# 16-TemHumdIr.net
KiCad netlist of a schematic drawn in Altium Designer
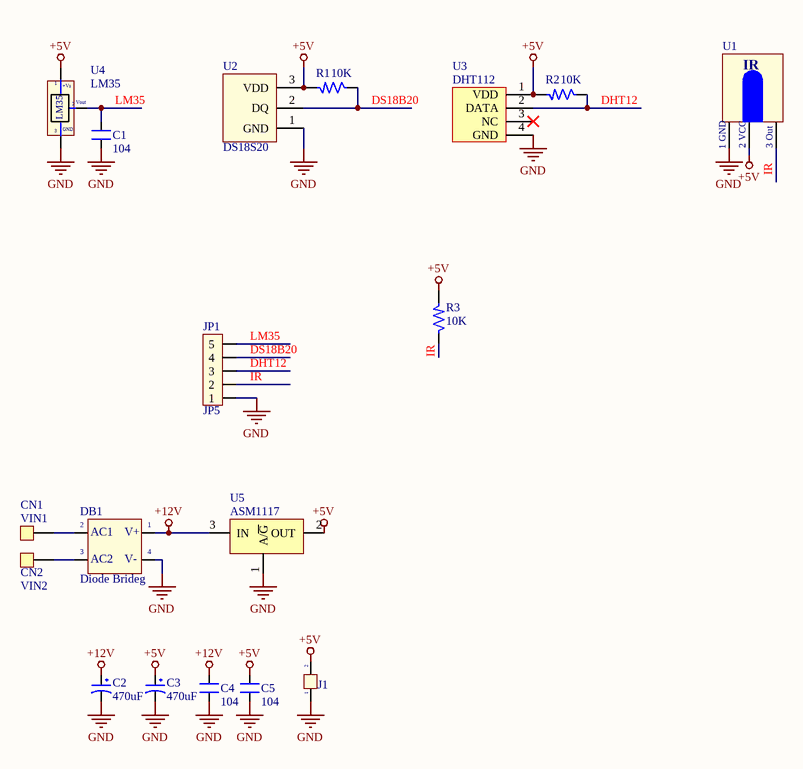
[diagram p0: 16-TemHumdIr.SchDoc]

(export (version "E")
  (design (tool "Eeschema 10.0.6"))
  (components
    (comp (ref "C1")
      (value "104")
      (footprint "C-0805")
      (fields (field (name "DESIGNED BY") "VanDungEvn"))
      (libsource (lib "syhaunguyen") (part "CN"))
    )
    (comp (ref "C2")
      (value "470uF")
      (footprint "C-ALU-D6.5")
      (description "Cap P  0,1uF < 22uF , 16 - 50V")
      (libsource (lib "PART") (part "CP1"))
    )
    (comp (ref "C3")
      (value "470uF")
      (footprint "C-ALU-D6.5")
      (description "Cap P  0,1uF < 22uF , 16 - 50V")
      (libsource (lib "PART") (part "CP1"))
    )
    (comp (ref "C4")
      (value "104")
      (footprint "C-0805")
      (fields (field (name "DESIGNED BY") "VanDungEvn"))
      (libsource (lib "syhaunguyen") (part "CN"))
    )
    (comp (ref "C5")
      (value "104")
      (footprint "C-0805")
      (fields (field (name "DESIGNED BY") "VanDungEvn"))
      (libsource (lib "syhaunguyen") (part "CN"))
    )
    (comp (ref "CN1")
      (value "VIN1")
      (footprint "M3")
      (libsource (lib "doAnTotNghiep2017Lib") (part "COCDONGM3"))
    )
    (comp (ref "CN2")
      (value "VIN2")
      (footprint "M3")
      (libsource (lib "doAnTotNghiep2017Lib") (part "COCDONGM3"))
    )
    (comp (ref "DB1")
      (value "Diode Brideg")
      (footprint "D-DB-1A-SMD")
      (description "Convert AC to DC voltage, 4 pin")
      (libsource (lib "PART") (part "DB"))
    )
    (comp (ref "J1") (value "Jumper 2") (footprint "JP2") (libsource (lib "syhaunguyen") (part "JP 2")))
    (comp (ref "JP1") (value "JP5") (footprint "JP5") (libsource (lib "syhaunguyen") (part "JP5")))
    (comp (ref "R1")
      (value "10K")
      (footprint "R-0805")
      (description "Resistor 1/4W")
      (libsource (lib "syhaunguyen") (part "R"))
    )
    (comp (ref "R2")
      (value "10K")
      (footprint "R-0805")
      (description "Resistor 1/4W")
      (libsource (lib "syhaunguyen") (part "R"))
    )
    (comp (ref "R3")
      (value "10K")
      (footprint "R-0805")
      (description "Resistor 1/4W")
      (libsource (lib "syhaunguyen") (part "R"))
    )
    (comp (ref "U1")
      (value "IR1")
      (footprint "IR-TSOP1133")
      (description "Receiver Infraed IC")
      (libsource (lib "PART") (part "IR1"))
    )
    (comp (ref "U2")
      (value "DS18S20")
      (footprint "TO-92AB")
      (description "High Precision  1-Wire® Digital Thermometer")
      (libsource (lib "syhaunguyen") (part "DS18S20"))
    )
    (comp (ref "U3") (value "DHT112") (footprint "DHT12") (libsource (lib "QLT_AIR_LIB") (part "DHT11")))
    (comp (ref "U4")
      (value "LM35")
      (footprint "QTO-92")
      (description "Teminal")
      (libsource (lib "syhaunguyen") (part "LM35"))
    )
    (comp (ref "U5")
      (value "ASM1117")
      (footprint "TO-252")
      (libsource (lib "doAnTotNghiep2017Lib") (part "ASM1117"))
    )
  )
  (nets
    (net (code "1") (name "+5V") (class "Default")
      (node (ref "C3") (pin "1") (pinfunction "1_1") (pintype "passive"))
      (node (ref "C5") (pin "2") (pinfunction "2_2") (pintype "passive"))
      (node (ref "J1") (pin "2") (pinfunction "2_2") (pintype "passive"))
      (node (ref "R1") (pin "2") (pinfunction "2_2") (pintype "passive"))
      (node (ref "R2") (pin "2") (pinfunction "2_2") (pintype "passive"))
      (node (ref "R3") (pin "2") (pinfunction "2_2") (pintype "passive"))
      (node (ref "U1") (pin "2") (pinfunction "GND_2") (pintype "passive"))
      (node (ref "U2") (pin "3") (pinfunction "VDD_3") (pintype "passive"))
      (node (ref "U3") (pin "1") (pinfunction "VDD_1") (pintype "passive"))
      (node (ref "U4") (pin "1") (pinfunction "+Vs_1") (pintype "passive"))
      (node (ref "U5") (pin "2") (pinfunction "OUT_2") (pintype "passive"))
    )
    (net (code "2") (name "+12V") (class "Default")
      (node (ref "C2") (pin "1") (pinfunction "1_1") (pintype "passive"))
      (node (ref "C4") (pin "2") (pinfunction "2_2") (pintype "passive"))
      (node (ref "DB1") (pin "3") (pinfunction "AC2_3") (pintype "passive"))
      (node (ref "U5") (pin "3") (pinfunction "IN_3") (pintype "passive"))
    )
    (net (code "3") (name "/DHT12") (class "Default")
      (node (ref "JP1") (pin "3") (pinfunction "3_3") (pintype "passive"))
      (node (ref "R2") (pin "1") (pinfunction "1_1") (pintype "passive"))
      (node (ref "U3") (pin "2") (pinfunction "DATA_2") (pintype "passive"))
    )
    (net (code "4") (name "/DS18B20") (class "Default")
      (node (ref "JP1") (pin "4") (pinfunction "4_4") (pintype "passive"))
      (node (ref "R1") (pin "1") (pinfunction "1_1") (pintype "passive"))
      (node (ref "U2") (pin "2") (pinfunction "DQ_2") (pintype "passive"))
    )
    (net (code "5") (name "/IR") (class "Default")
      (node (ref "JP1") (pin "2") (pinfunction "2_2") (pintype "passive"))
      (node (ref "R3") (pin "1") (pinfunction "1_1") (pintype "passive"))
      (node (ref "U1") (pin "3") (pinfunction "VCC_3") (pintype "passive"))
    )
    (net (code "6") (name "/LM35") (class "Default")
      (node (ref "C1") (pin "2") (pinfunction "2_2") (pintype "passive"))
      (node (ref "JP1") (pin "5") (pinfunction "5_5") (pintype "passive"))
      (node (ref "U4") (pin "2") (pinfunction "Vout_2") (pintype "passive"))
    )
    (net (code "7") (name "GND") (class "Default")
      (node (ref "C1") (pin "1") (pinfunction "1_1") (pintype "passive"))
      (node (ref "C2") (pin "2") (pinfunction "2_2") (pintype "passive"))
      (node (ref "C3") (pin "2") (pinfunction "2_2") (pintype "passive"))
      (node (ref "C4") (pin "1") (pinfunction "1_1") (pintype "passive"))
      (node (ref "C5") (pin "1") (pinfunction "1_1") (pintype "passive"))
      (node (ref "DB1") (pin "4") (pinfunction "-V_OUT_4") (pintype "passive"))
      (node (ref "J1") (pin "1") (pinfunction "1_1") (pintype "passive"))
      (node (ref "JP1") (pin "1") (pinfunction "1_1") (pintype "passive"))
      (node (ref "U1") (pin "1") (pinfunction "Out_1") (pintype "passive"))
      (node (ref "U2") (pin "1") (pinfunction "GND_1") (pintype "passive"))
      (node (ref "U3") (pin "4") (pinfunction "GND_4") (pintype "passive"))
      (node (ref "U4") (pin "3") (pinfunction "-_3") (pintype "passive"))
      (node (ref "U5") (pin "1") (pinfunction "A/~{G}_1") (pintype "passive"))
    )
    (net (code "8") (name "Net-(DB1-+V_OUT)") (class "Default")
      (node (ref "CN2") (pin "1") (pintype "passive"))
      (node (ref "DB1") (pin "1") (pinfunction "+V_OUT_1") (pintype "passive"))
    )
    (net (code "9") (name "Net-(DB1-AC1)") (class "Default")
      (node (ref "CN1") (pin "1") (pintype "passive"))
      (node (ref "DB1") (pin "2") (pinfunction "AC1_2") (pintype "passive"))
    )
    (net (code "10") (name "unconnected-(U3-NC-Pad3)") (class "Default")
      (node (ref "U3") (pin "3") (pinfunction "NC_3") (pintype "passive+no_connect"))
    )
  )
)
